# prototype_card.net
KiCad netlist of a schematic drawn in EAGLE
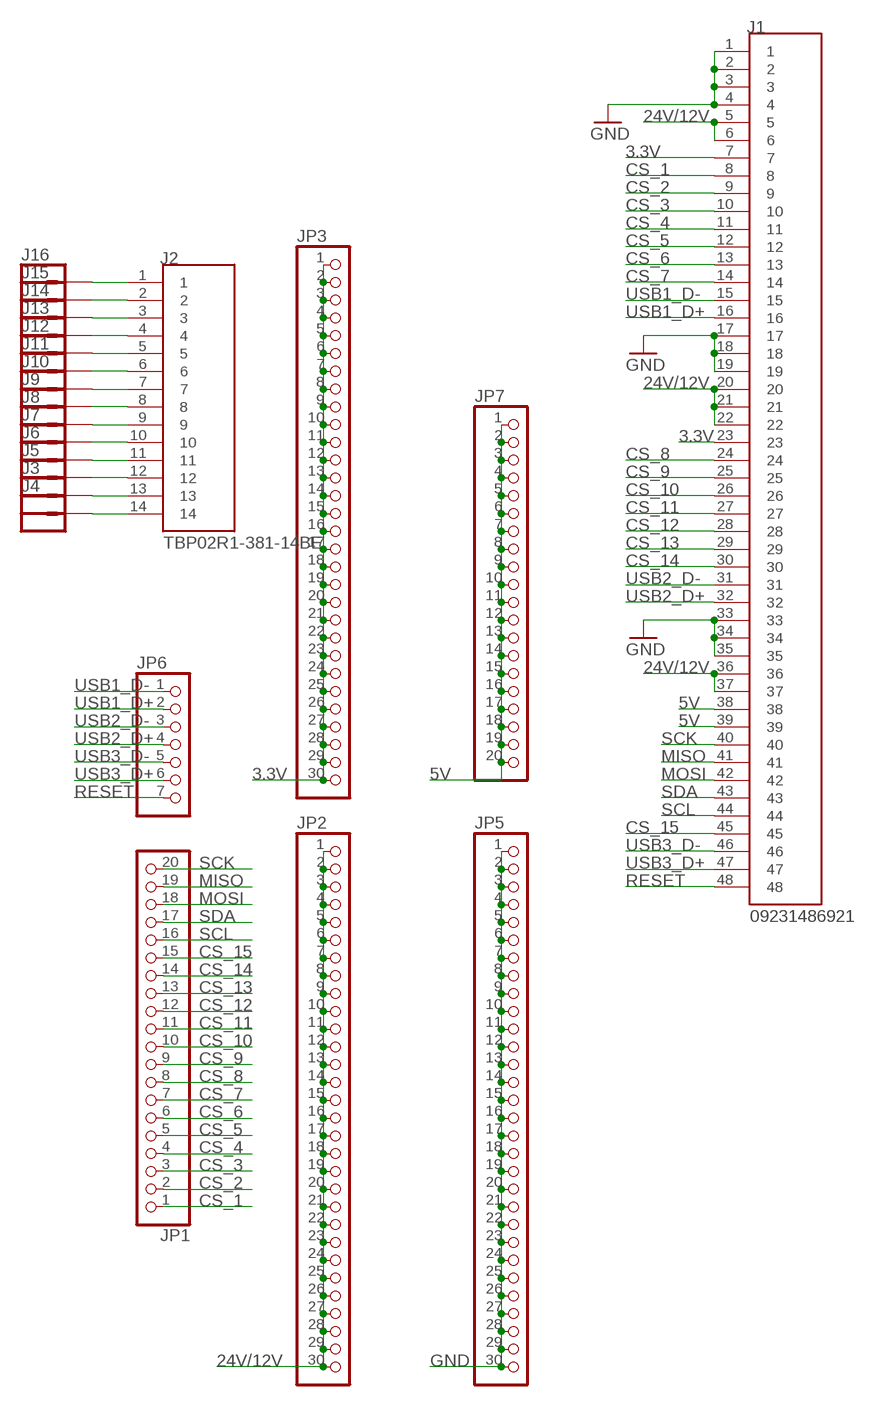
[diagram p0: schematic, sheet 1]

(export (version "E")
  (design (tool "Eeschema 10.0.6"))
  (components
    (comp (ref "J1")
      (value "09231486921")
      (footprint "eagle-import:HARTING_09231486921")
      (libsource (lib "eagle-import") (part "09231486921"))
    )
    (comp (ref "J2")
      (value "TBP02R1-381-14BE")
      (footprint "eagle-import:CUI_TBP02R1-381-14BE")
      (libsource (lib "eagle-import") (part "TBP02R1-381-14BE"))
    )
    (comp (ref "J3")
      (value "CONN_01PTH_LONGPAD")
      (footprint "eagle-import:1X01_LONGPAD")
      (libsource (lib "eagle-import") (part "CONN_01PTH_LONGPAD"))
    )
    (comp (ref "J4")
      (value "CONN_01PTH_LONGPAD")
      (footprint "eagle-import:1X01_LONGPAD")
      (libsource (lib "eagle-import") (part "CONN_01PTH_LONGPAD"))
    )
    (comp (ref "J5")
      (value "CONN_01PTH_LONGPAD")
      (footprint "eagle-import:1X01_LONGPAD")
      (libsource (lib "eagle-import") (part "CONN_01PTH_LONGPAD"))
    )
    (comp (ref "J6")
      (value "CONN_01PTH_LONGPAD")
      (footprint "eagle-import:1X01_LONGPAD")
      (libsource (lib "eagle-import") (part "CONN_01PTH_LONGPAD"))
    )
    (comp (ref "J7")
      (value "CONN_01PTH_LONGPAD")
      (footprint "eagle-import:1X01_LONGPAD")
      (libsource (lib "eagle-import") (part "CONN_01PTH_LONGPAD"))
    )
    (comp (ref "J8")
      (value "CONN_01PTH_LONGPAD")
      (footprint "eagle-import:1X01_LONGPAD")
      (libsource (lib "eagle-import") (part "CONN_01PTH_LONGPAD"))
    )
    (comp (ref "J9")
      (value "CONN_01PTH_LONGPAD")
      (footprint "eagle-import:1X01_LONGPAD")
      (libsource (lib "eagle-import") (part "CONN_01PTH_LONGPAD"))
    )
    (comp (ref "J10")
      (value "CONN_01PTH_LONGPAD")
      (footprint "eagle-import:1X01_LONGPAD")
      (libsource (lib "eagle-import") (part "CONN_01PTH_LONGPAD"))
    )
    (comp (ref "J11")
      (value "CONN_01PTH_LONGPAD")
      (footprint "eagle-import:1X01_LONGPAD")
      (libsource (lib "eagle-import") (part "CONN_01PTH_LONGPAD"))
    )
    (comp (ref "J12")
      (value "CONN_01PTH_LONGPAD")
      (footprint "eagle-import:1X01_LONGPAD")
      (libsource (lib "eagle-import") (part "CONN_01PTH_LONGPAD"))
    )
    (comp (ref "J13")
      (value "CONN_01PTH_LONGPAD")
      (footprint "eagle-import:1X01_LONGPAD")
      (libsource (lib "eagle-import") (part "CONN_01PTH_LONGPAD"))
    )
    (comp (ref "J14")
      (value "CONN_01PTH_LONGPAD")
      (footprint "eagle-import:1X01_LONGPAD")
      (libsource (lib "eagle-import") (part "CONN_01PTH_LONGPAD"))
    )
    (comp (ref "J15")
      (value "CONN_01PTH_LONGPAD")
      (footprint "eagle-import:1X01_LONGPAD")
      (libsource (lib "eagle-import") (part "CONN_01PTH_LONGPAD"))
    )
    (comp (ref "J16")
      (value "CONN_01PTH_LONGPAD")
      (footprint "eagle-import:1X01_LONGPAD")
      (libsource (lib "eagle-import") (part "CONN_01PTH_LONGPAD"))
    )
    (comp (ref "JP1")
      (value "PINHD-1X20")
      (footprint "eagle-import:1X20")
      (libsource (lib "eagle-import") (part "PINHD-1X20"))
    )
    (comp (ref "JP2")
      (value "PINHD-1X30")
      (footprint "eagle-import:1X30")
      (libsource (lib "eagle-import") (part "PINHD-1X30"))
    )
    (comp (ref "JP3")
      (value "PINHD-1X30")
      (footprint "eagle-import:1X30")
      (libsource (lib "eagle-import") (part "PINHD-1X30"))
    )
    (comp (ref "JP5")
      (value "PINHD-1X30")
      (footprint "eagle-import:1X30")
      (libsource (lib "eagle-import") (part "PINHD-1X30"))
    )
    (comp (ref "JP6")
      (value "PINHD-1X7")
      (footprint "eagle-import:1X07")
      (libsource (lib "eagle-import") (part "PINHD-1X7"))
    )
    (comp (ref "JP7")
      (value "PINHD-1X20")
      (footprint "eagle-import:1X20")
      (libsource (lib "eagle-import") (part "PINHD-1X20"))
    )
  )
  (nets
    (net (code "1") (name "/3.3V") (class "Default")
      (node (ref "J1") (pin "23") (pinfunction "23_23") (pintype "passive"))
      (node (ref "J1") (pin "7") (pinfunction "7_7") (pintype "passive"))
      (node (ref "JP3") (pin "1") (pinfunction "1_1") (pintype "passive"))
      (node (ref "JP3") (pin "10") (pinfunction "10_10") (pintype "passive"))
      (node (ref "JP3") (pin "11") (pinfunction "11_11") (pintype "passive"))
      (node (ref "JP3") (pin "12") (pinfunction "12_12") (pintype "passive"))
      (node (ref "JP3") (pin "13") (pinfunction "13_13") (pintype "passive"))
      (node (ref "JP3") (pin "14") (pinfunction "14_14") (pintype "passive"))
      (node (ref "JP3") (pin "15") (pinfunction "15_15") (pintype "passive"))
      (node (ref "JP3") (pin "16") (pinfunction "16_16") (pintype "passive"))
      (node (ref "JP3") (pin "17") (pinfunction "17_17") (pintype "passive"))
      (node (ref "JP3") (pin "18") (pinfunction "18_18") (pintype "passive"))
      (node (ref "JP3") (pin "19") (pinfunction "19_19") (pintype "passive"))
      (node (ref "JP3") (pin "2") (pinfunction "2_2") (pintype "passive"))
      (node (ref "JP3") (pin "20") (pinfunction "20_20") (pintype "passive"))
      (node (ref "JP3") (pin "21") (pinfunction "21_21") (pintype "passive"))
      (node (ref "JP3") (pin "22") (pinfunction "22_22") (pintype "passive"))
      (node (ref "JP3") (pin "23") (pinfunction "23_23") (pintype "passive"))
      (node (ref "JP3") (pin "24") (pinfunction "24_24") (pintype "passive"))
      (node (ref "JP3") (pin "25") (pinfunction "25_25") (pintype "passive"))
      (node (ref "JP3") (pin "26") (pinfunction "26_26") (pintype "passive"))
      (node (ref "JP3") (pin "27") (pinfunction "27_27") (pintype "passive"))
      (node (ref "JP3") (pin "28") (pinfunction "28_28") (pintype "passive"))
      (node (ref "JP3") (pin "29") (pinfunction "29_29") (pintype "passive"))
      (node (ref "JP3") (pin "3") (pinfunction "3_3") (pintype "passive"))
      (node (ref "JP3") (pin "30") (pinfunction "30_30") (pintype "passive"))
      (node (ref "JP3") (pin "4") (pinfunction "4_4") (pintype "passive"))
      (node (ref "JP3") (pin "5") (pinfunction "5_5") (pintype "passive"))
      (node (ref "JP3") (pin "6") (pinfunction "6_6") (pintype "passive"))
      (node (ref "JP3") (pin "7") (pinfunction "7_7") (pintype "passive"))
      (node (ref "JP3") (pin "8") (pinfunction "8_8") (pintype "passive"))
      (node (ref "JP3") (pin "9") (pinfunction "9_9") (pintype "passive"))
    )
    (net (code "2") (name "/5V") (class "Default")
      (node (ref "J1") (pin "38") (pinfunction "38_38") (pintype "passive"))
      (node (ref "J1") (pin "39") (pinfunction "39_39") (pintype "passive"))
      (node (ref "JP7") (pin "1") (pinfunction "1_1") (pintype "passive"))
      (node (ref "JP7") (pin "10") (pinfunction "10_10") (pintype "passive"))
      (node (ref "JP7") (pin "11") (pinfunction "11_11") (pintype "passive"))
      (node (ref "JP7") (pin "12") (pinfunction "12_12") (pintype "passive"))
      (node (ref "JP7") (pin "13") (pinfunction "13_13") (pintype "passive"))
      (node (ref "JP7") (pin "14") (pinfunction "14_14") (pintype "passive"))
      (node (ref "JP7") (pin "15") (pinfunction "15_15") (pintype "passive"))
      (node (ref "JP7") (pin "16") (pinfunction "16_16") (pintype "passive"))
      (node (ref "JP7") (pin "17") (pinfunction "17_17") (pintype "passive"))
      (node (ref "JP7") (pin "18") (pinfunction "18_18") (pintype "passive"))
      (node (ref "JP7") (pin "19") (pinfunction "19_19") (pintype "passive"))
      (node (ref "JP7") (pin "2") (pinfunction "2_2") (pintype "passive"))
      (node (ref "JP7") (pin "20") (pinfunction "20_20") (pintype "passive"))
      (node (ref "JP7") (pin "3") (pinfunction "3_3") (pintype "passive"))
      (node (ref "JP7") (pin "4") (pinfunction "4_4") (pintype "passive"))
      (node (ref "JP7") (pin "5") (pinfunction "5_5") (pintype "passive"))
      (node (ref "JP7") (pin "6") (pinfunction "6_6") (pintype "passive"))
      (node (ref "JP7") (pin "7") (pinfunction "7_7") (pintype "passive"))
      (node (ref "JP7") (pin "8") (pinfunction "8_8") (pintype "passive"))
      (node (ref "JP7") (pin "9") (pinfunction "9_9") (pintype "passive"))
    )
    (net (code "3") (name "/24V{slash}12V") (class "Default")
      (node (ref "J1") (pin "20") (pinfunction "20_20") (pintype "passive"))
      (node (ref "J1") (pin "21") (pinfunction "21_21") (pintype "passive"))
      (node (ref "J1") (pin "22") (pinfunction "22_22") (pintype "passive"))
      (node (ref "J1") (pin "36") (pinfunction "36_36") (pintype "passive"))
      (node (ref "J1") (pin "37") (pinfunction "37_37") (pintype "passive"))
      (node (ref "J1") (pin "5") (pinfunction "5_5") (pintype "passive"))
      (node (ref "J1") (pin "6") (pinfunction "6_6") (pintype "passive"))
      (node (ref "JP2") (pin "1") (pinfunction "1_1") (pintype "passive"))
      (node (ref "JP2") (pin "10") (pinfunction "10_10") (pintype "passive"))
      (node (ref "JP2") (pin "11") (pinfunction "11_11") (pintype "passive"))
      (node (ref "JP2") (pin "12") (pinfunction "12_12") (pintype "passive"))
      (node (ref "JP2") (pin "13") (pinfunction "13_13") (pintype "passive"))
      (node (ref "JP2") (pin "14") (pinfunction "14_14") (pintype "passive"))
      (node (ref "JP2") (pin "15") (pinfunction "15_15") (pintype "passive"))
      (node (ref "JP2") (pin "16") (pinfunction "16_16") (pintype "passive"))
      (node (ref "JP2") (pin "17") (pinfunction "17_17") (pintype "passive"))
      (node (ref "JP2") (pin "18") (pinfunction "18_18") (pintype "passive"))
      (node (ref "JP2") (pin "19") (pinfunction "19_19") (pintype "passive"))
      (node (ref "JP2") (pin "2") (pinfunction "2_2") (pintype "passive"))
      (node (ref "JP2") (pin "20") (pinfunction "20_20") (pintype "passive"))
      (node (ref "JP2") (pin "21") (pinfunction "21_21") (pintype "passive"))
      (node (ref "JP2") (pin "22") (pinfunction "22_22") (pintype "passive"))
      (node (ref "JP2") (pin "23") (pinfunction "23_23") (pintype "passive"))
      (node (ref "JP2") (pin "24") (pinfunction "24_24") (pintype "passive"))
      (node (ref "JP2") (pin "25") (pinfunction "25_25") (pintype "passive"))
      (node (ref "JP2") (pin "26") (pinfunction "26_26") (pintype "passive"))
      (node (ref "JP2") (pin "27") (pinfunction "27_27") (pintype "passive"))
      (node (ref "JP2") (pin "28") (pinfunction "28_28") (pintype "passive"))
      (node (ref "JP2") (pin "29") (pinfunction "29_29") (pintype "passive"))
      (node (ref "JP2") (pin "3") (pinfunction "3_3") (pintype "passive"))
      (node (ref "JP2") (pin "30") (pinfunction "30_30") (pintype "passive"))
      (node (ref "JP2") (pin "4") (pinfunction "4_4") (pintype "passive"))
      (node (ref "JP2") (pin "5") (pinfunction "5_5") (pintype "passive"))
      (node (ref "JP2") (pin "6") (pinfunction "6_6") (pintype "passive"))
      (node (ref "JP2") (pin "7") (pinfunction "7_7") (pintype "passive"))
      (node (ref "JP2") (pin "8") (pinfunction "8_8") (pintype "passive"))
      (node (ref "JP2") (pin "9") (pinfunction "9_9") (pintype "passive"))
    )
    (net (code "4") (name "/CS_1") (class "Default")
      (node (ref "J1") (pin "8") (pinfunction "8_8") (pintype "passive"))
      (node (ref "JP1") (pin "1") (pinfunction "1_1") (pintype "passive"))
    )
    (net (code "5") (name "/CS_2") (class "Default")
      (node (ref "J1") (pin "9") (pinfunction "9_9") (pintype "passive"))
      (node (ref "JP1") (pin "2") (pinfunction "2_2") (pintype "passive"))
    )
    (net (code "6") (name "/CS_3") (class "Default")
      (node (ref "J1") (pin "10") (pinfunction "10_10") (pintype "passive"))
      (node (ref "JP1") (pin "3") (pinfunction "3_3") (pintype "passive"))
    )
    (net (code "7") (name "/CS_4") (class "Default")
      (node (ref "J1") (pin "11") (pinfunction "11_11") (pintype "passive"))
      (node (ref "JP1") (pin "4") (pinfunction "4_4") (pintype "passive"))
    )
    (net (code "8") (name "/CS_5") (class "Default")
      (node (ref "J1") (pin "12") (pinfunction "12_12") (pintype "passive"))
      (node (ref "JP1") (pin "5") (pinfunction "5_5") (pintype "passive"))
    )
    (net (code "9") (name "/CS_6") (class "Default")
      (node (ref "J1") (pin "13") (pinfunction "13_13") (pintype "passive"))
      (node (ref "JP1") (pin "6") (pinfunction "6_6") (pintype "passive"))
    )
    (net (code "10") (name "/CS_7") (class "Default")
      (node (ref "J1") (pin "14") (pinfunction "14_14") (pintype "passive"))
      (node (ref "JP1") (pin "7") (pinfunction "7_7") (pintype "passive"))
    )
    (net (code "11") (name "/CS_8") (class "Default")
      (node (ref "J1") (pin "24") (pinfunction "24_24") (pintype "passive"))
      (node (ref "JP1") (pin "8") (pinfunction "8_8") (pintype "passive"))
    )
    (net (code "12") (name "/CS_9") (class "Default")
      (node (ref "J1") (pin "25") (pinfunction "25_25") (pintype "passive"))
      (node (ref "JP1") (pin "9") (pinfunction "9_9") (pintype "passive"))
    )
    (net (code "13") (name "/CS_10") (class "Default")
      (node (ref "J1") (pin "26") (pinfunction "26_26") (pintype "passive"))
      (node (ref "JP1") (pin "10") (pinfunction "10_10") (pintype "passive"))
    )
    (net (code "14") (name "/CS_11") (class "Default")
      (node (ref "J1") (pin "27") (pinfunction "27_27") (pintype "passive"))
      (node (ref "JP1") (pin "11") (pinfunction "11_11") (pintype "passive"))
    )
    (net (code "15") (name "/CS_12") (class "Default")
      (node (ref "J1") (pin "28") (pinfunction "28_28") (pintype "passive"))
      (node (ref "JP1") (pin "12") (pinfunction "12_12") (pintype "passive"))
    )
    (net (code "16") (name "/CS_13") (class "Default")
      (node (ref "J1") (pin "29") (pinfunction "29_29") (pintype "passive"))
      (node (ref "JP1") (pin "13") (pinfunction "13_13") (pintype "passive"))
    )
    (net (code "17") (name "/CS_14") (class "Default")
      (node (ref "J1") (pin "30") (pinfunction "30_30") (pintype "passive"))
      (node (ref "JP1") (pin "14") (pinfunction "14_14") (pintype "passive"))
    )
    (net (code "18") (name "/CS_15") (class "Default")
      (node (ref "J1") (pin "45") (pinfunction "45_45") (pintype "passive"))
      (node (ref "JP1") (pin "15") (pinfunction "15_15") (pintype "passive"))
    )
    (net (code "19") (name "/MISO") (class "Default")
      (node (ref "J1") (pin "41") (pinfunction "41_41") (pintype "passive"))
      (node (ref "JP1") (pin "19") (pinfunction "19_19") (pintype "passive"))
    )
    (net (code "20") (name "/MOSI") (class "Default")
      (node (ref "J1") (pin "42") (pinfunction "42_42") (pintype "passive"))
      (node (ref "JP1") (pin "18") (pinfunction "18_18") (pintype "passive"))
    )
    (net (code "21") (name "/RESET") (class "Default")
      (node (ref "J1") (pin "48") (pinfunction "48_48") (pintype "passive"))
      (node (ref "JP6") (pin "7") (pinfunction "7_7") (pintype "passive"))
    )
    (net (code "22") (name "/SCK") (class "Default")
      (node (ref "J1") (pin "40") (pinfunction "40_40") (pintype "passive"))
      (node (ref "JP1") (pin "20") (pinfunction "20_20") (pintype "passive"))
    )
    (net (code "23") (name "/SCL") (class "Default")
      (node (ref "J1") (pin "44") (pinfunction "44_44") (pintype "passive"))
      (node (ref "JP1") (pin "16") (pinfunction "16_16") (pintype "passive"))
    )
    (net (code "24") (name "/SDA") (class "Default")
      (node (ref "J1") (pin "43") (pinfunction "43_43") (pintype "passive"))
      (node (ref "JP1") (pin "17") (pinfunction "17_17") (pintype "passive"))
    )
    (net (code "25") (name "/USB1_D+") (class "Default")
      (node (ref "J1") (pin "16") (pinfunction "16_16") (pintype "passive"))
      (node (ref "JP6") (pin "2") (pinfunction "2_2") (pintype "passive"))
    )
    (net (code "26") (name "/USB1_D-") (class "Default")
      (node (ref "J1") (pin "15") (pinfunction "15_15") (pintype "passive"))
      (node (ref "JP6") (pin "1") (pinfunction "1_1") (pintype "passive"))
    )
    (net (code "27") (name "/USB2_D+") (class "Default")
      (node (ref "J1") (pin "32") (pinfunction "32_32") (pintype "passive"))
      (node (ref "JP6") (pin "4") (pinfunction "4_4") (pintype "passive"))
    )
    (net (code "28") (name "/USB2_D-") (class "Default")
      (node (ref "J1") (pin "31") (pinfunction "31_31") (pintype "passive"))
      (node (ref "JP6") (pin "3") (pinfunction "3_3") (pintype "passive"))
    )
    (net (code "29") (name "/USB3_D+") (class "Default")
      (node (ref "J1") (pin "47") (pinfunction "47_47") (pintype "passive"))
      (node (ref "JP6") (pin "6") (pinfunction "6_6") (pintype "passive"))
    )
    (net (code "30") (name "/USB3_D-") (class "Default")
      (node (ref "J1") (pin "46") (pinfunction "46_46") (pintype "passive"))
      (node (ref "JP6") (pin "5") (pinfunction "5_5") (pintype "passive"))
    )
    (net (code "31") (name "GND") (class "Default")
      (node (ref "J1") (pin "1") (pinfunction "1_1") (pintype "passive"))
      (node (ref "J1") (pin "17") (pinfunction "17_17") (pintype "passive"))
      (node (ref "J1") (pin "18") (pinfunction "18_18") (pintype "passive"))
      (node (ref "J1") (pin "19") (pinfunction "19_19") (pintype "passive"))
      (node (ref "J1") (pin "2") (pinfunction "2_2") (pintype "passive"))
      (node (ref "J1") (pin "3") (pinfunction "3_3") (pintype "passive"))
      (node (ref "J1") (pin "33") (pinfunction "33_33") (pintype "passive"))
      (node (ref "J1") (pin "34") (pinfunction "34_34") (pintype "passive"))
      (node (ref "J1") (pin "35") (pinfunction "35_35") (pintype "passive"))
      (node (ref "J1") (pin "4") (pinfunction "4_4") (pintype "passive"))
      (node (ref "JP5") (pin "1") (pinfunction "1_1") (pintype "passive"))
      (node (ref "JP5") (pin "10") (pinfunction "10_10") (pintype "passive"))
      (node (ref "JP5") (pin "11") (pinfunction "11_11") (pintype "passive"))
      (node (ref "JP5") (pin "12") (pinfunction "12_12") (pintype "passive"))
      (node (ref "JP5") (pin "13") (pinfunction "13_13") (pintype "passive"))
      (node (ref "JP5") (pin "14") (pinfunction "14_14") (pintype "passive"))
      (node (ref "JP5") (pin "15") (pinfunction "15_15") (pintype "passive"))
      (node (ref "JP5") (pin "16") (pinfunction "16_16") (pintype "passive"))
      (node (ref "JP5") (pin "17") (pinfunction "17_17") (pintype "passive"))
      (node (ref "JP5") (pin "18") (pinfunction "18_18") (pintype "passive"))
      (node (ref "JP5") (pin "19") (pinfunction "19_19") (pintype "passive"))
      (node (ref "JP5") (pin "2") (pinfunction "2_2") (pintype "passive"))
      (node (ref "JP5") (pin "20") (pinfunction "20_20") (pintype "passive"))
      (node (ref "JP5") (pin "21") (pinfunction "21_21") (pintype "passive"))
      (node (ref "JP5") (pin "22") (pinfunction "22_22") (pintype "passive"))
      (node (ref "JP5") (pin "23") (pinfunction "23_23") (pintype "passive"))
      (node (ref "JP5") (pin "24") (pinfunction "24_24") (pintype "passive"))
      (node (ref "JP5") (pin "25") (pinfunction "25_25") (pintype "passive"))
      (node (ref "JP5") (pin "26") (pinfunction "26_26") (pintype "passive"))
      (node (ref "JP5") (pin "27") (pinfunction "27_27") (pintype "passive"))
      (node (ref "JP5") (pin "28") (pinfunction "28_28") (pintype "passive"))
      (node (ref "JP5") (pin "29") (pinfunction "29_29") (pintype "passive"))
      (node (ref "JP5") (pin "3") (pinfunction "3_3") (pintype "passive"))
      (node (ref "JP5") (pin "30") (pinfunction "30_30") (pintype "passive"))
      (node (ref "JP5") (pin "4") (pinfunction "4_4") (pintype "passive"))
      (node (ref "JP5") (pin "5") (pinfunction "5_5") (pintype "passive"))
      (node (ref "JP5") (pin "6") (pinfunction "6_6") (pintype "passive"))
      (node (ref "JP5") (pin "7") (pinfunction "7_7") (pintype "passive"))
      (node (ref "JP5") (pin "8") (pinfunction "8_8") (pintype "passive"))
      (node (ref "JP5") (pin "9") (pinfunction "9_9") (pintype "passive"))
    )
    (net (code "32") (name "Net-(J2-Pad8)") (class "Default")
      (node (ref "J2") (pin "8") (pinfunction "8_8") (pintype "passive"))
      (node (ref "J9") (pin "1") (pinfunction "1_1") (pintype "passive"))
    )
    (net (code "33") (name "Net-(J2-Pad9)") (class "Default")
      (node (ref "J2") (pin "9") (pinfunction "9_9") (pintype "passive"))
      (node (ref "J8") (pin "1") (pinfunction "1_1") (pintype "passive"))
    )
    (net (code "34") (name "Net-(J2-Pad10)") (class "Default")
      (node (ref "J2") (pin "10") (pinfunction "10_10") (pintype "passive"))
      (node (ref "J7") (pin "1") (pinfunction "1_1") (pintype "passive"))
    )
    (net (code "35") (name "Net-(J2-Pad11)") (class "Default")
      (node (ref "J2") (pin "11") (pinfunction "11_11") (pintype "passive"))
      (node (ref "J6") (pin "1") (pinfunction "1_1") (pintype "passive"))
    )
    (net (code "36") (name "Net-(J2-Pad12)") (class "Default")
      (node (ref "J2") (pin "12") (pinfunction "12_12") (pintype "passive"))
      (node (ref "J5") (pin "1") (pinfunction "1_1") (pintype "passive"))
    )
    (net (code "37") (name "Net-(J2-Pad13)") (class "Default")
      (node (ref "J2") (pin "13") (pinfunction "13_13") (pintype "passive"))
      (node (ref "J3") (pin "1") (pinfunction "1_1") (pintype "passive"))
    )
    (net (code "38") (name "Net-(J2-Pad14)") (class "Default")
      (node (ref "J2") (pin "14") (pinfunction "14_14") (pintype "passive"))
      (node (ref "J4") (pin "1") (pinfunction "1_1") (pintype "passive"))
    )
    (net (code "39") (name "Net-(J10-Pad1)") (class "Default")
      (node (ref "J10") (pin "1") (pinfunction "1_1") (pintype "passive"))
      (node (ref "J2") (pin "7") (pinfunction "7_7") (pintype "passive"))
    )
    (net (code "40") (name "Net-(J11-Pad1)") (class "Default")
      (node (ref "J11") (pin "1") (pinfunction "1_1") (pintype "passive"))
      (node (ref "J2") (pin "6") (pinfunction "6_6") (pintype "passive"))
    )
    (net (code "41") (name "Net-(J12-Pad1)") (class "Default")
      (node (ref "J12") (pin "1") (pinfunction "1_1") (pintype "passive"))
      (node (ref "J2") (pin "5") (pinfunction "5_5") (pintype "passive"))
    )
    (net (code "42") (name "Net-(J13-Pad1)") (class "Default")
      (node (ref "J13") (pin "1") (pinfunction "1_1") (pintype "passive"))
      (node (ref "J2") (pin "4") (pinfunction "4_4") (pintype "passive"))
    )
    (net (code "43") (name "Net-(J14-Pad1)") (class "Default")
      (node (ref "J14") (pin "1") (pinfunction "1_1") (pintype "passive"))
      (node (ref "J2") (pin "3") (pinfunction "3_3") (pintype "passive"))
    )
    (net (code "44") (name "Net-(J15-Pad1)") (class "Default")
      (node (ref "J15") (pin "1") (pinfunction "1_1") (pintype "passive"))
      (node (ref "J2") (pin "2") (pinfunction "2_2") (pintype "passive"))
    )
    (net (code "45") (name "Net-(J16-Pad1)") (class "Default")
      (node (ref "J16") (pin "1") (pinfunction "1_1") (pintype "passive"))
      (node (ref "J2") (pin "1") (pinfunction "1_1") (pintype "passive"))
    )
  )
)
